# PC.net
KiCad netlist of a schematic drawn in Altium Designer
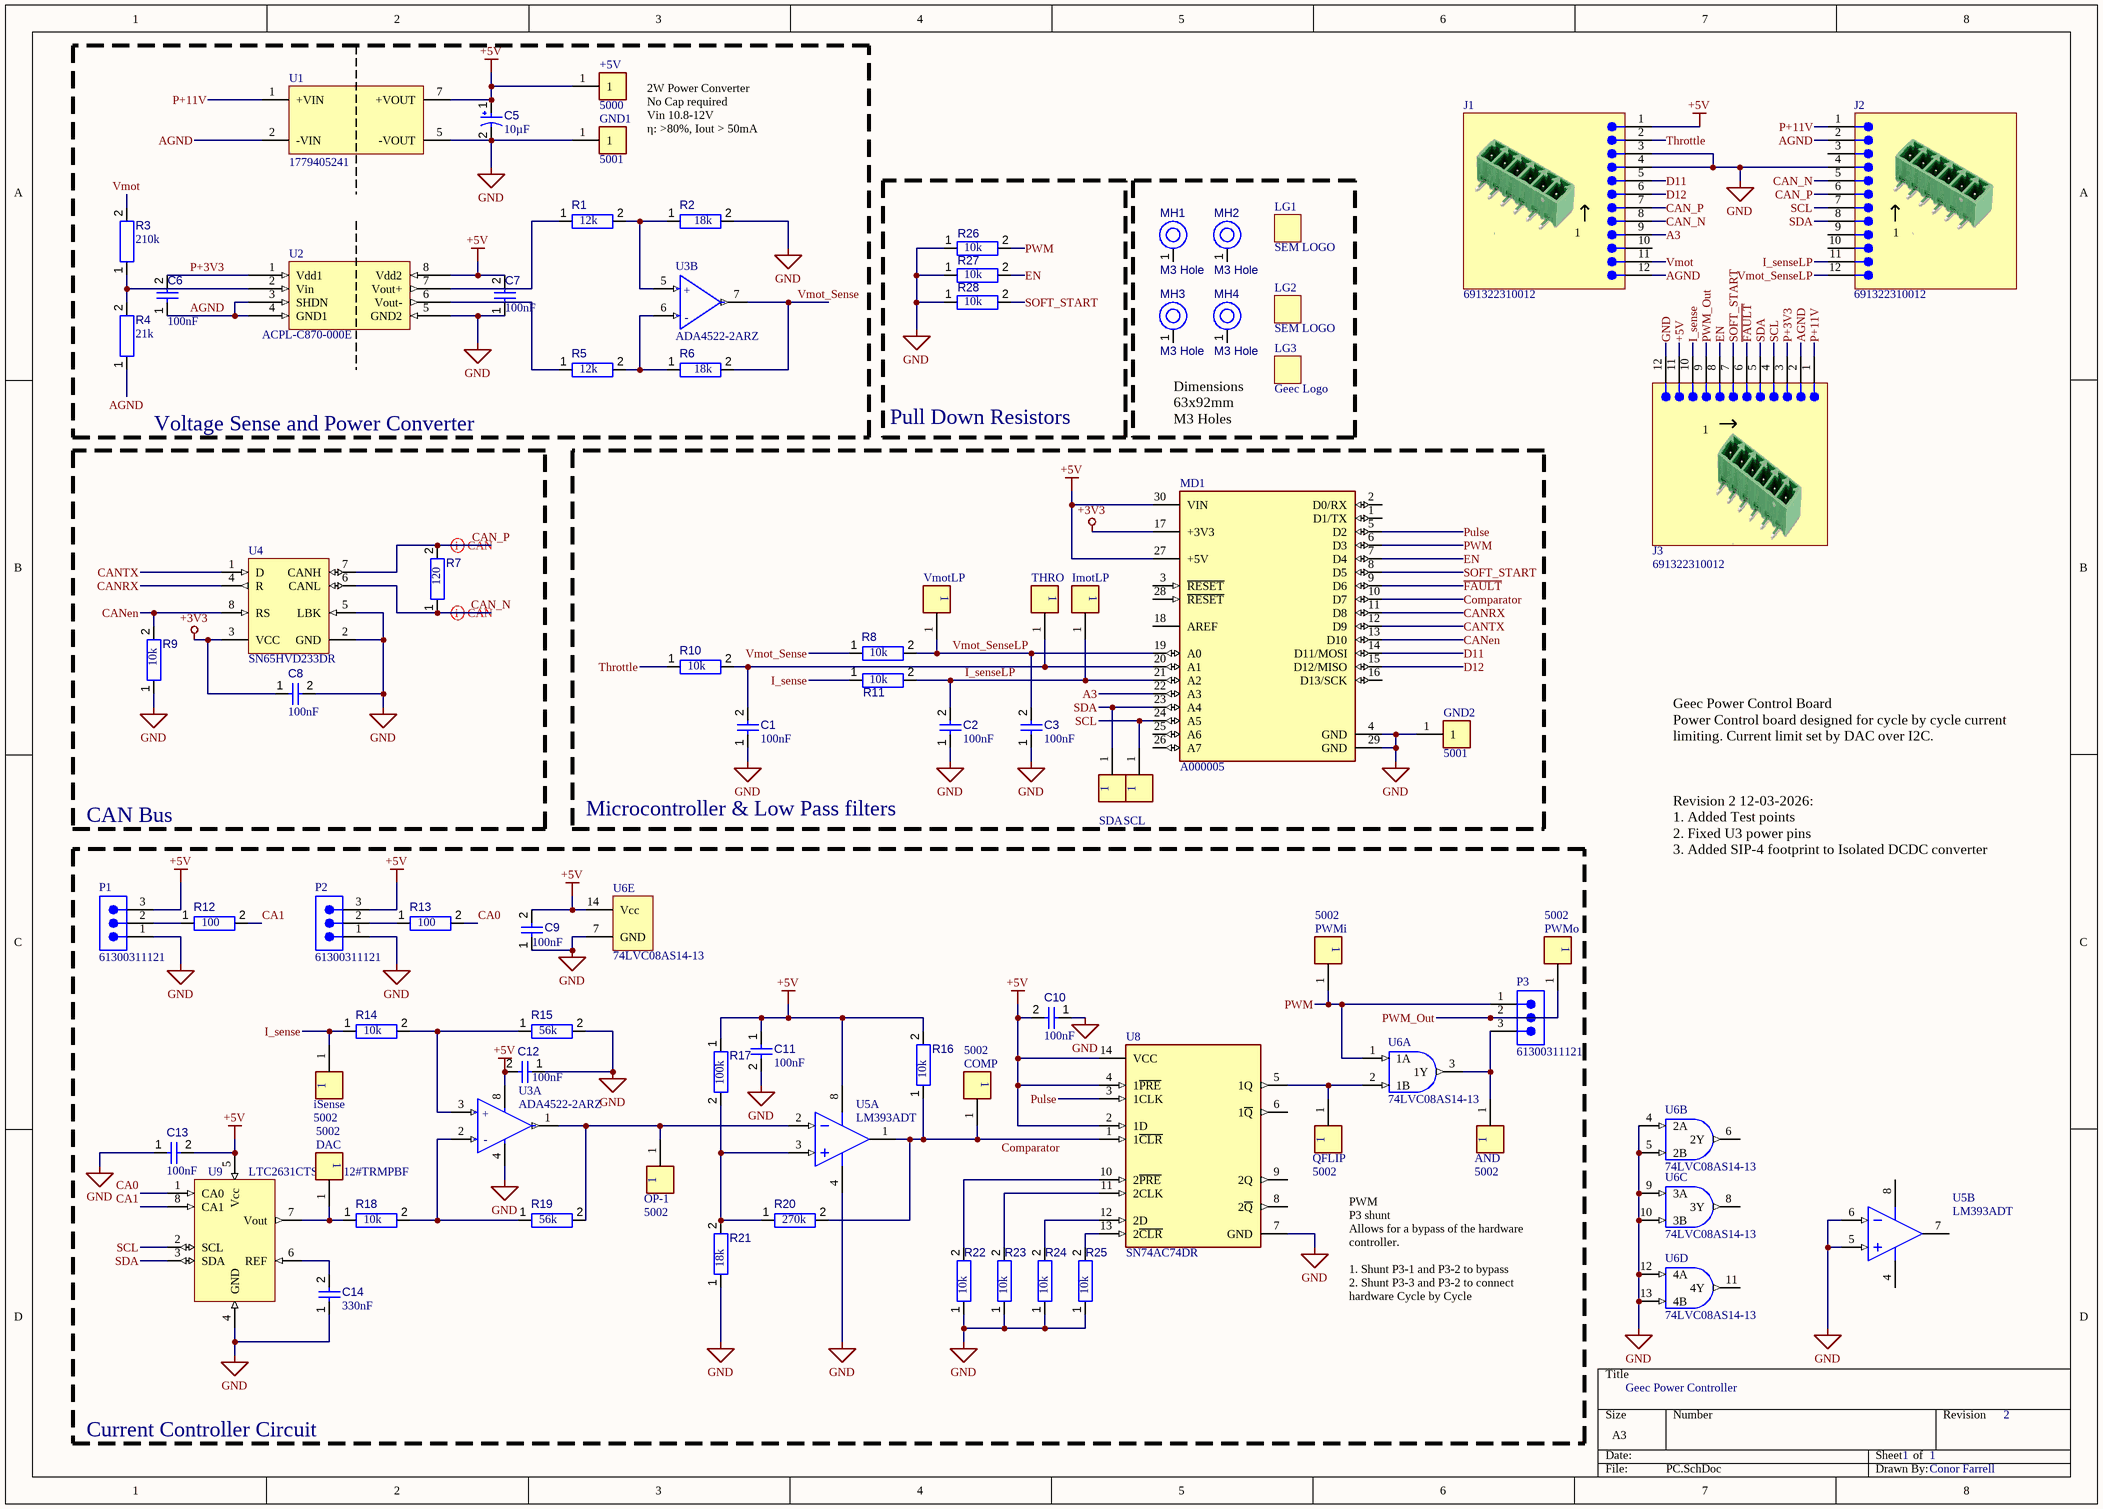
[diagram p0: PC.SchDoc]

(export (version "E")
  (design (tool "Eeschema 10.0.6"))
  (components
    (comp (ref "+5V")
      (value "5000")
      (footprint "FP-5000-MFG")
      (description "Cable Wrap, 1/2 Inch, Polyethylene, Natural, 50 Ft, Spirap Series")
      (libsource (lib "") (part "1e4615820a309e3ce90f9e6d957b7fa_2"))
    )
    (comp (ref "AND")
      (value "5002")
      (footprint "FP-5002-MFG")
      (description "Test Point, Mini, Thm, Pc, .300 L, .100 Od, Heat Resistant Nylon 46, White")
      (libsource (lib "University of Galway") (part "1e4615820a309e3ce90f9e6d957b7fa"))
    )
    (comp (ref "C1")
      (value "100nF")
      (footprint "Cap-THT-Ceramic(7.2X2.5)")
      (description "100nF, Throughhole Film Capacitor, 5mm spacing")
      (fields (field (name "TOLERANCE") "10%") (field (name "Comment") "100n-THT"))
      (libsource (lib "University of Galway") (part "CAP-NP-2"))
    )
    (comp (ref "C2")
      (value "100nF")
      (footprint "Cap-THT-Ceramic(7.2X2.5)")
      (description "100nF, Throughhole Film Capacitor, 5mm spacing")
      (fields (field (name "TOLERANCE") "10%") (field (name "Comment") "100n-THT"))
      (libsource (lib "University of Galway") (part "CAP-NP-2"))
    )
    (comp (ref "C3")
      (value "100nF")
      (footprint "Cap-THT-Ceramic(7.2X2.5)")
      (description "100nF, Throughhole Film Capacitor, 5mm spacing")
      (fields (field (name "TOLERANCE") "10%") (field (name "Comment") "100n-THT"))
      (libsource (lib "University of Galway") (part "CAP-NP-2"))
    )
    (comp (ref "C5")
      (value "10µF")
      (footprint "CAPPR55-200-1100X500X1200")
      (description "Aluminum Electrolytic Capacitor, 10 uF, +/- 20%, 50 V, -40 to 85 degC, 2-Pin THD, RoHS, Bulk")
      (fields (field (name "MANUFACTURER") "Panasonic") (field (name "TOLERANCE") "20%"))
      (libsource (lib "University of Galway") (part "CAP-P-2"))
    )
    (comp (ref "C6")
      (value "100nF")
      (footprint "Cap-THT-Ceramic(7.2X2.5)")
      (description "100nF, Throughhole Film Capacitor, 5mm spacing")
      (fields (field (name "TOLERANCE") "10%") (field (name "Comment") "100n-THT"))
      (libsource (lib "University of Galway") (part "CAP-NP-2"))
    )
    (comp (ref "C7")
      (value "100nF")
      (footprint "Cap-THT-Ceramic(7.2X2.5)")
      (description "100nF, Throughhole Film Capacitor, 5mm spacing")
      (fields (field (name "TOLERANCE") "10%") (field (name "Comment") "100n-THT"))
      (libsource (lib "University of Galway") (part "CAP-NP-2"))
    )
    (comp (ref "C8")
      (value "100nF")
      (footprint "Cap-THT-Ceramic(7.2X2.5)")
      (description "100nF, Throughhole Film Capacitor, 5mm spacing")
      (fields (field (name "TOLERANCE") "10%") (field (name "Comment") "100n-THT"))
      (libsource (lib "University of Galway") (part "CAP-NP-2"))
    )
    (comp (ref "C9")
      (value "100nF")
      (footprint "Cap-THT-Ceramic(7.2X2.5)")
      (description "100nF, Throughhole Film Capacitor, 5mm spacing")
      (fields (field (name "TOLERANCE") "10%") (field (name "Comment") "100n-THT"))
      (libsource (lib "University of Galway") (part "CAP-NP-2"))
    )
    (comp (ref "C10")
      (value "100nF")
      (footprint "Cap-THT-Ceramic(7.2X2.5)")
      (description "100nF, Throughhole Film Capacitor, 5mm spacing")
      (fields (field (name "TOLERANCE") "10%") (field (name "Comment") "100n-THT"))
      (libsource (lib "University of Galway") (part "CAP-NP-2"))
    )
    (comp (ref "C11")
      (value "100nF")
      (footprint "Cap-THT-Ceramic(7.2X2.5)")
      (description "100nF, Throughhole Film Capacitor, 5mm spacing")
      (fields (field (name "TOLERANCE") "10%") (field (name "Comment") "100n-THT"))
      (libsource (lib "University of Galway") (part "CAP-NP-2"))
    )
    (comp (ref "C12")
      (value "100nF")
      (footprint "Cap-THT-Ceramic(7.2X2.5)")
      (description "100nF, Throughhole Film Capacitor, 5mm spacing")
      (fields (field (name "TOLERANCE") "10%") (field (name "Comment") "100n-THT"))
      (libsource (lib "University of Galway") (part "CAP-NP-2"))
    )
    (comp (ref "C13")
      (value "100nF")
      (footprint "Cap-THT-Ceramic(7.2X2.5)")
      (description "100nF, Throughhole Film Capacitor, 5mm spacing")
      (fields (field (name "TOLERANCE") "10%") (field (name "Comment") "100n-THT"))
      (libsource (lib "University of Galway") (part "CAP-NP-2"))
    )
    (comp (ref "C14")
      (value "330nF")
      (footprint "Cap-THT-Ceramic(7.2X2.5)")
      (description "330nF, Throughhole Film Capacitor, 5mm spacing")
      (fields (field (name "TOLERANCE") "10%") (field (name "Comment") "330nF-THT-Film"))
      (libsource (lib "University of Galway") (part "CAP-NP-2"))
    )
    (comp (ref "COMP")
      (value "5002")
      (footprint "FP-5002-MFG")
      (description "Test Point, Mini, Thm, Pc, .300 L, .100 Od, Heat Resistant Nylon 46, White")
      (libsource (lib "") (part "1e4615820a309e3ce90f9e6d957b7fa_1"))
    )
    (comp (ref "DAC")
      (value "5002")
      (footprint "FP-5002-MFG")
      (description "Test Point, Mini, Thm, Pc, .300 L, .100 Od, Heat Resistant Nylon 46, White")
      (libsource (lib "") (part "1e4615820a309e3ce90f9e6d957b7fa_1"))
    )
    (comp (ref "GND1")
      (value "5001")
      (footprint "FP-5001-MFG")
      (description "Test Point, Mini, Thm, Pc, .300 L, .100 Od, Heat Resistant Nylon 46, Black")
      (libsource (lib "") (part "1e4615820a309e3ce90f9e6d957b7fa_2"))
    )
    (comp (ref "GND2")
      (value "5001")
      (footprint "FP-5001-MFG")
      (description "Test Point, Mini, Thm, Pc, .300 L, .100 Od, Heat Resistant Nylon 46, Black")
      (libsource (lib "") (part "1e4615820a309e3ce90f9e6d957b7fa_2"))
    )
    (comp (ref "ImotLP")
      (value "5002")
      (footprint "FP-5002-MFG")
      (description "Test Point, Mini, Thm, Pc, .300 L, .100 Od, Heat Resistant Nylon 46, White")
      (libsource (lib "") (part "1e4615820a309e3ce90f9e6d957b7fa_1"))
    )
    (comp (ref "iSense")
      (value "5002")
      (footprint "FP-5002-MFG")
      (description "Test Point, Mini, Thm, Pc, .300 L, .100 Od, Heat Resistant Nylon 46, White")
      (libsource (lib "University of Galway") (part "1e4615820a309e3ce90f9e6d957b7fa"))
    )
    (comp (ref "J1")
      (value "691322310012")
      (footprint "691322310012")
      (description "Terminal Block, R/A Header, 12Pos, Th Rohs Compliant: Yes")
      (libsource (lib "University of Galway") (part "TBL - 1R - 12P - Male"))
    )
    (comp (ref "J2")
      (value "691322310012")
      (footprint "691322310012")
      (description "Terminal Block, R/A Header, 12Pos, Th Rohs Compliant: Yes")
      (libsource (lib "") (part "TBL - 1R - 12P - Male_1"))
    )
    (comp (ref "J3")
      (value "691322310012")
      (footprint "691322310012")
      (description "Terminal Block, R/A Header, 12Pos, Th Rohs Compliant: Yes")
      (libsource (lib "University of Galway") (part "TBL - 1R - 12P - Male"))
    )
    (comp (ref "LG1")
      (value "SEM LOGO")
      (footprint "SEM LOGO-Footprint-1")
      (description "SEM Logo Required for Power Electronics")
      (libsource (lib "University of Galway") (part "SEM LOGO-Symbol-1"))
    )
    (comp (ref "LG2")
      (value "SEM LOGO")
      (footprint "SEM LOGO-Footprint-1")
      (description "SEM Logo Required for Power Electronics")
      (libsource (lib "University of Galway") (part "SEM LOGO-Symbol-1"))
    )
    (comp (ref "LG3")
      (value "Geec Logo")
      (footprint "Geec Logo-Footprint-1")
      (libsource (lib "University of Galway") (part "Geec Logo-Symbol-1"))
    )
    (comp (ref "MD1")
      (value "A000005")
      (footprint "FP-A000005-MFG")
      (description "ATmega328 Microcontroller Development Board 16MHz CPU 2KB RAM 1KB/32KB EEPROM/Flash")
      (libsource (lib "University of Galway") (part "d190c066e99afd1c6882cf92e11b2cc"))
    )
    (comp (ref "MH1")
      (value "M3 Hole")
      (footprint "M3 Hole-Footprint-1")
      (description "Hole for M3 bolt")
      (libsource (lib "University of Galway") (part "CMP-00028-00000-1"))
    )
    (comp (ref "MH2")
      (value "M3 Hole")
      (footprint "M3 Hole-Footprint-1")
      (description "Hole for M3 bolt")
      (libsource (lib "University of Galway") (part "CMP-00028-00000-1"))
    )
    (comp (ref "MH3")
      (value "M3 Hole")
      (footprint "M3 Hole-Footprint-1")
      (description "Hole for M3 bolt")
      (libsource (lib "University of Galway") (part "CMP-00028-00000-1"))
    )
    (comp (ref "MH4")
      (value "M3 Hole")
      (footprint "M3 Hole-Footprint-1")
      (description "Hole for M3 bolt")
      (libsource (lib "University of Galway") (part "CMP-00028-00000-1"))
    )
    (comp (ref "OP-1")
      (value "5002")
      (footprint "FP-5002-MFG")
      (description "Test Point, Mini, Thm, Pc, .300 L, .100 Od, Heat Resistant Nylon 46, White")
      (libsource (lib "University of Galway") (part "1e4615820a309e3ce90f9e6d957b7fa"))
    )
    (comp (ref "P1")
      (value "61300311121")
      (footprint "61300311121")
      (description "WR-PHD Pin Header, THT, Vertical, pitch 2.54mm, 1 Row, 3P")
      (fields (field (name "MANUFACTURER") "Wurth Elektronik"))
      (libsource (lib "University of Galway") (part "62000311121"))
    )
    (comp (ref "P2")
      (value "61300311121")
      (footprint "61300311121")
      (description "WR-PHD Pin Header, THT, Vertical, pitch 2.54mm, 1 Row, 3P")
      (fields (field (name "MANUFACTURER") "Wurth Elektronik"))
      (libsource (lib "University of Galway") (part "62000311121"))
    )
    (comp (ref "P3")
      (value "61300311121")
      (footprint "61300311121")
      (description "WR-PHD Pin Header, THT, Vertical, pitch 2.54mm, 1 Row, 3P")
      (fields (field (name "MANUFACTURER") "Wurth Elektronik"))
      (libsource (lib "University of Galway") (part "62000311121"))
    )
    (comp (ref "PWMi")
      (value "5002")
      (footprint "FP-5002-MFG")
      (description "Test Point, Mini, Thm, Pc, .300 L, .100 Od, Heat Resistant Nylon 46, White")
      (libsource (lib "") (part "1e4615820a309e3ce90f9e6d957b7fa_1"))
    )
    (comp (ref "PWMo")
      (value "5002")
      (footprint "FP-5002-MFG")
      (description "Test Point, Mini, Thm, Pc, .300 L, .100 Od, Heat Resistant Nylon 46, White")
      (libsource (lib "") (part "1e4615820a309e3ce90f9e6d957b7fa_1"))
    )
    (comp (ref "QFLIP")
      (value "5002")
      (footprint "FP-5002-MFG")
      (description "Test Point, Mini, Thm, Pc, .300 L, .100 Od, Heat Resistant Nylon 46, White")
      (libsource (lib "University of Galway") (part "1e4615820a309e3ce90f9e6d957b7fa"))
    )
    (comp (ref "R1")
      (value "12k")
      (footprint "RESA60-630X240")
      (description "10kOhm Resistor, Through Hole, 1/4W")
      (fields (field (name "POWER") "250mW") (field (name "TOLERANCE") "5%"))
      (libsource (lib "University of Galway") (part "RES-2"))
    )
    (comp (ref "R2")
      (value "18k")
      (footprint "RESA60-630X240")
      (description "10kOhm Resistor, Through Hole, 1/4W")
      (fields (field (name "POWER") "250mW") (field (name "TOLERANCE") "5%"))
      (libsource (lib "University of Galway") (part "RES-2"))
    )
    (comp (ref "R3")
      (value "210k")
      (footprint "RESA60-630X240")
      (description "210kOhm Resistor, Throughhole, 1/4W")
      (fields (field (name "TOLERANCE") "5%") (field (name "POWER") "250mW"))
      (libsource (lib "University of Galway") (part "RES-2"))
    )
    (comp (ref "R4")
      (value "21k")
      (footprint "RESA60-630X240")
      (description "21kOhm Resistor, Throughhole, 1/4W")
      (fields (field (name "TOLERANCE") "5%") (field (name "POWER") "250mW"))
      (libsource (lib "University of Galway") (part "RES-2"))
    )
    (comp (ref "R5")
      (value "12k")
      (footprint "RESA60-630X240")
      (description "10kOhm Resistor, Through Hole, 1/4W")
      (fields (field (name "POWER") "250mW") (field (name "TOLERANCE") "5%"))
      (libsource (lib "University of Galway") (part "RES-2"))
    )
    (comp (ref "R6")
      (value "18k")
      (footprint "RESA60-630X240")
      (description "10kOhm Resistor, Through Hole, 1/4W")
      (fields (field (name "POWER") "250mW") (field (name "TOLERANCE") "5%"))
      (libsource (lib "University of Galway") (part "RES-2"))
    )
    (comp (ref "R7")
      (value "120")
      (footprint "RESA60-630X240")
      (description "120Ohm Resistor, Through Hole, 1/4W")
      (fields (field (name "TOLERANCE") "5%") (field (name "POWER") "250mW"))
      (libsource (lib "University of Galway") (part "RES-2"))
    )
    (comp (ref "R8")
      (value "10k")
      (footprint "RESA60-630X240")
      (description "10kOhm Resistor, Through Hole, 1/4W")
      (fields (field (name "POWER") "250mW") (field (name "TOLERANCE") "5%"))
      (libsource (lib "University of Galway") (part "RES-2"))
    )
    (comp (ref "R9")
      (value "10k")
      (footprint "RESA60-630X240")
      (description "10kOhm Resistor, Through Hole, 1/4W")
      (fields (field (name "POWER") "250mW") (field (name "TOLERANCE") "5%"))
      (libsource (lib "University of Galway") (part "RES-2"))
    )
    (comp (ref "R10")
      (value "10k")
      (footprint "RESA60-630X240")
      (description "10kOhm Resistor, Through Hole, 1/4W")
      (fields (field (name "POWER") "250mW") (field (name "TOLERANCE") "5%"))
      (libsource (lib "University of Galway") (part "RES-2"))
    )
    (comp (ref "R11")
      (value "10k")
      (footprint "RESA60-630X240")
      (description "10kOhm Resistor, Through Hole, 1/4W")
      (fields (field (name "POWER") "250mW") (field (name "TOLERANCE") "5%"))
      (libsource (lib "University of Galway") (part "RES-2"))
    )
    (comp (ref "R12")
      (value "100")
      (footprint "RESA60-630X240")
      (description "100Ohm Resistor Through Hole 1/4W")
      (fields (field (name "TOLERANCE") "5%") (field (name "POWER") "250mW"))
      (libsource (lib "University of Galway") (part "RES-2"))
    )
    (comp (ref "R13")
      (value "100")
      (footprint "RESA60-630X240")
      (description "100Ohm Resistor Through Hole 1/4W")
      (fields (field (name "TOLERANCE") "5%") (field (name "POWER") "250mW"))
      (libsource (lib "University of Galway") (part "RES-2"))
    )
    (comp (ref "R14")
      (value "10k")
      (footprint "RESA60-630X240")
      (description "10kOhm Resistor, Through Hole, 1/4W")
      (fields (field (name "POWER") "250mW") (field (name "TOLERANCE") "5%"))
      (libsource (lib "University of Galway") (part "RES-2"))
    )
    (comp (ref "R15")
      (value "56k")
      (footprint "RESA60-630X240")
      (description "100kOhm Resistor, Through hole, 250mW")
      (fields (field (name "TOLERANCE") "5%") (field (name "POWER") "250mW"))
      (libsource (lib "University of Galway") (part "RES-2"))
    )
    (comp (ref "R16")
      (value "10k")
      (footprint "RESA60-630X240")
      (description "10kOhm Resistor, Through Hole, 1/4W")
      (fields (field (name "POWER") "250mW") (field (name "TOLERANCE") "5%"))
      (libsource (lib "University of Galway") (part "RES-2"))
    )
    (comp (ref "R17")
      (value "100k")
      (footprint "RESA60-630X240")
      (description "100kOhm Resistor, Through hole, 250mW")
      (fields (field (name "TOLERANCE") "5%") (field (name "POWER") "250mW"))
      (libsource (lib "University of Galway") (part "RES-2"))
    )
    (comp (ref "R18")
      (value "10k")
      (footprint "RESA60-630X240")
      (description "10kOhm Resistor, Through Hole, 1/4W")
      (fields (field (name "POWER") "250mW") (field (name "TOLERANCE") "5%"))
      (libsource (lib "University of Galway") (part "RES-2"))
    )
    (comp (ref "R19")
      (value "56k")
      (footprint "RESA60-630X240")
      (description "100kOhm Resistor, Through hole, 250mW")
      (fields (field (name "TOLERANCE") "5%") (field (name "POWER") "250mW"))
      (libsource (lib "University of Galway") (part "RES-2"))
    )
    (comp (ref "R20")
      (value "270k")
      (footprint "RESA60-630X240")
      (description "270kOhm Resistor, Through Hole, 1/4W")
      (fields (field (name "TOLERANCE") "5%") (field (name "POWER") "250mW"))
      (libsource (lib "University of Galway") (part "RES-2"))
    )
    (comp (ref "R21")
      (value "18k")
      (footprint "RESA60-630X240")
      (description "18kOhm Resistor, Through Hole, 1/4W")
      (fields (field (name "POWER") "250mW") (field (name "TOLERANCE") "5%"))
      (libsource (lib "University of Galway") (part "RES-2"))
    )
    (comp (ref "R22")
      (value "10k")
      (footprint "RESA60-630X240")
      (description "10kOhm Resistor, Through Hole, 1/4W")
      (fields (field (name "POWER") "250mW") (field (name "TOLERANCE") "5%"))
      (libsource (lib "University of Galway") (part "RES-2"))
    )
    (comp (ref "R23")
      (value "10k")
      (footprint "RESA60-630X240")
      (description "10kOhm Resistor, Through Hole, 1/4W")
      (fields (field (name "POWER") "250mW") (field (name "TOLERANCE") "5%"))
      (libsource (lib "University of Galway") (part "RES-2"))
    )
    (comp (ref "R24")
      (value "10k")
      (footprint "RESA60-630X240")
      (description "10kOhm Resistor, Through Hole, 1/4W")
      (fields (field (name "POWER") "250mW") (field (name "TOLERANCE") "5%"))
      (libsource (lib "University of Galway") (part "RES-2"))
    )
    (comp (ref "R25")
      (value "10k")
      (footprint "RESA60-630X240")
      (description "10kOhm Resistor, Through Hole, 1/4W")
      (fields (field (name "POWER") "250mW") (field (name "TOLERANCE") "5%"))
      (libsource (lib "University of Galway") (part "RES-2"))
    )
    (comp (ref "R26")
      (value "10k")
      (footprint "RESA60-630X240")
      (description "10kOhm Resistor, Through Hole, 1/4W")
      (fields (field (name "POWER") "250mW") (field (name "TOLERANCE") "5%"))
      (libsource (lib "University of Galway") (part "RES-2"))
    )
    (comp (ref "R27")
      (value "10k")
      (footprint "RESA60-630X240")
      (description "10kOhm Resistor, Through Hole, 1/4W")
      (fields (field (name "POWER") "250mW") (field (name "TOLERANCE") "5%"))
      (libsource (lib "University of Galway") (part "RES-2"))
    )
    (comp (ref "R28")
      (value "10k")
      (footprint "RESA60-630X240")
      (description "10kOhm Resistor, Through Hole, 1/4W")
      (fields (field (name "POWER") "250mW") (field (name "TOLERANCE") "5%"))
      (libsource (lib "University of Galway") (part "RES-2"))
    )
    (comp (ref "SCL")
      (value "5002")
      (footprint "FP-5002-MFG")
      (description "Test Point, Mini, Thm, Pc, .300 L, .100 Od, Heat Resistant Nylon 46, White")
      (libsource (lib "University of Galway") (part "1e4615820a309e3ce90f9e6d957b7fa"))
    )
    (comp (ref "SDA")
      (value "5002")
      (footprint "FP-5002-MFG")
      (description "Test Point, Mini, Thm, Pc, .300 L, .100 Od, Heat Resistant Nylon 46, White")
      (libsource (lib "University of Galway") (part "1e4615820a309e3ce90f9e6d957b7fa"))
    )
    (comp (ref "THRO")
      (value "5002")
      (footprint "FP-5002-MFG")
      (description "Test Point, Mini, Thm, Pc, .300 L, .100 Od, Heat Resistant Nylon 46, White")
      (libsource (lib "") (part "1e4615820a309e3ce90f9e6d957b7fa_1"))
    )
    (comp (ref "U1")
      (value "1779405241")
      (footprint "SIP-7_1779405241")
      (description "WPME-FISM Fixed Isolated Module, SIP-7, 10.8 - 13.2 Vin, 5 Vout")
      (fields (field (name "MANUFACTURER") "Wurth Elektronik"))
      (libsource (lib "University of Galway") (part "1779405341"))
    )
    (comp (ref "U2")
      (value "ACPL-C870-000E")
      (footprint "SOIC127P1150X173-8M")
      (description "IC OPAMP ISOLATION 1 CIRC 8SO Isolation Amplifier 1 Circuit Differential 8-SO Stretched")
      (libsource (lib "University of Galway") (part "ACPL-C870-000E-Symbol-1"))
    )
    (comp (ref "U3")
      (value "ADA4522-2ARZ")
      (footprint "FP-R-8-IPC_C")
      (description "IC OPAMP ZERO-DRIFT 2 CIRC 8SOIC Zero-Drift Amplifier 2 Circuit Rail-to-Rail 8-SOIC")
      (libsource (lib "University of Galway") (part "9970287e766f5f2538295826f6e31b6"))
    )
    (comp (ref "U4")
      (value "SN65HVD233DR")
      (footprint "D0008A_L")
      (description "3.3 V CAN Transceiver with Standby Mode, Loopback 8-SOIC -40 to 125")
      (libsource (lib "University of Galway") (part "TI-SN65HVD233-SOIC_D-8"))
    )
    (comp (ref "U5")
      (value "LM393ADT")
      (footprint "ONSC-SOIC-8-751-07_AJ_V")
      (description "LM393 Series Dual 36 V 100 nA SMT Low Power Voltage Comparator - SOIC-8")
      (libsource (lib "University of Galway") (part "LM393ADT"))
    )
    (comp (ref "U6")
      (value "74LVC08AS14-13")
      (footprint "SOIC127P600X173-14N")
      (description "74LVC Series 5.5 V Surface Mount Quadruple 2-Input AND Gate - SOIC-14")
      (libsource (lib "University of Galway") (part "74LVC08AS14-13-Symbol-1"))
    )
    (comp (ref "U8")
      (value "SN74AC74DR")
      (footprint "FP-D0014A-MFG")
      (description "Dual Positive-Edge-Triggered D-Type Flip-Flops With Clear and Preset 14-SOIC -40 to 85")
      (libsource (lib "University of Galway") (part "46dc5e7b01fb147492ebe6268096ef7"))
    )
    (comp (ref "U9")
      (value "LTC2631CTS8-HZ12#TRMPBF")
      (footprint "TSOP65P280X100-8N")
      (description "IC DAC 12BIT V-OUT TSOT23-8 12 Bit Digital to Analog Converter 1 TSOT-23-8")
      (libsource (lib "University of Galway") (part "LTC2631CTS8-HZ12#TRMPBF-Symbol-1"))
    )
    (comp (ref "VmotLP")
      (value "5002")
      (footprint "FP-5002-MFG")
      (description "Test Point, Mini, Thm, Pc, .300 L, .100 Od, Heat Resistant Nylon 46, White")
      (libsource (lib "") (part "1e4615820a309e3ce90f9e6d957b7fa_1"))
    )
  )
  (nets
    (net (code "1") (name "+3V3") (class "Default")
      (node (ref "C8") (pin "1") (pinfunction "1_1") (pintype "passive"))
      (node (ref "MD1") (pin "17") (pinfunction "+3V3_17") (pintype "power_in"))
      (node (ref "U4") (pin "3") (pinfunction "VCC_3") (pintype "power_in"))
    )
    (net (code "2") (name "+5V") (class "Default")
      (node (ref "+5V") (pin "1") (pinfunction "1_1") (pintype "passive"))
      (node (ref "C10") (pin "2") (pinfunction "2_2") (pintype "passive"))
      (node (ref "C11") (pin "1") (pinfunction "1_1") (pintype "passive"))
      (node (ref "C12") (pin "2") (pinfunction "2_2") (pintype "passive"))
      (node (ref "C13") (pin "2") (pinfunction "2_2") (pintype "passive"))
      (node (ref "C5") (pin "1") (pinfunction "1_1") (pintype "passive"))
      (node (ref "C7") (pin "2") (pinfunction "2_2") (pintype "passive"))
      (node (ref "C9") (pin "2") (pinfunction "2_2") (pintype "passive"))
      (node (ref "J1") (pin "1") (pinfunction "1_1") (pintype "passive"))
      (node (ref "J3") (pin "11") (pinfunction "11_11") (pintype "passive"))
      (node (ref "MD1") (pin "27") (pinfunction "+5V_27") (pintype "power_in"))
      (node (ref "MD1") (pin "30") (pinfunction "VIN_30") (pintype "power_in"))
      (node (ref "P1") (pin "3") (pinfunction "3_3") (pintype "passive"))
      (node (ref "P2") (pin "3") (pinfunction "3_3") (pintype "passive"))
      (node (ref "R16") (pin "2") (pinfunction "2_2") (pintype "passive"))
      (node (ref "R17") (pin "1") (pinfunction "1_1") (pintype "passive"))
      (node (ref "U1") (pin "7") (pinfunction "+VOUT_7") (pintype "passive"))
      (node (ref "U2") (pin "8") (pinfunction "Vdd2_8") (pintype "input"))
      (node (ref "U3") (pin "8") (pinfunction "V+_8") (pintype "power_in"))
      (node (ref "U5") (pin "8") (pinfunction "VCC_8") (pintype "power_in"))
      (node (ref "U6") (pin "14") (pinfunction "Vcc_14") (pintype "passive"))
      (node (ref "U8") (pin "14") (pinfunction "VCC_14") (pintype "power_in"))
      (node (ref "U8") (pin "2") (pinfunction "1D_2") (pintype "input"))
      (node (ref "U8") (pin "4") (pinfunction "1~{PRE}_4") (pintype "input"))
      (node (ref "U9") (pin "5") (pinfunction "Vcc_5") (pintype "input"))
    )
    (net (code "3") (name "/A3") (class "Default")
      (node (ref "J1") (pin "9") (pinfunction "9_9") (pintype "passive"))
      (node (ref "MD1") (pin "22") (pinfunction "A3_22") (pintype "bidirectional"))
    )
    (net (code "4") (name "/AGND") (class "Default")
      (node (ref "C6") (pin "1") (pinfunction "1_1") (pintype "passive"))
      (node (ref "J1") (pin "12") (pinfunction "12_12") (pintype "passive"))
      (node (ref "J2") (pin "2") (pinfunction "2_2") (pintype "passive"))
      (node (ref "J3") (pin "2") (pinfunction "2_2") (pintype "passive"))
      (node (ref "R4") (pin "1") (pinfunction "1_1") (pintype "passive"))
      (node (ref "U1") (pin "2") (pinfunction "-VIN_2") (pintype "passive"))
      (node (ref "U2") (pin "3") (pinfunction "SHDN_3") (pintype "input"))
      (node (ref "U2") (pin "4") (pinfunction "GND1_4") (pintype "input"))
    )
    (net (code "5") (name "/CA0") (class "Default")
      (node (ref "R13") (pin "2") (pinfunction "2_2") (pintype "passive"))
      (node (ref "U9") (pin "1") (pinfunction "CA0_1") (pintype "input"))
    )
    (net (code "6") (name "/CA1") (class "Default")
      (node (ref "R12") (pin "2") (pinfunction "2_2") (pintype "passive"))
      (node (ref "U9") (pin "8") (pinfunction "CA1_8") (pintype "input"))
    )
    (net (code "7") (name "/CANRX") (class "Default")
      (node (ref "MD1") (pin "11") (pinfunction "D8_11") (pintype "bidirectional"))
      (node (ref "U4") (pin "4") (pinfunction "R_4") (pintype "output"))
    )
    (net (code "8") (name "/CANTX") (class "Default")
      (node (ref "MD1") (pin "12") (pinfunction "D9_12") (pintype "bidirectional"))
      (node (ref "U4") (pin "1") (pinfunction "D_1") (pintype "input"))
    )
    (net (code "9") (name "/CAN_N") (class "Default")
      (node (ref "J1") (pin "8") (pinfunction "8_8") (pintype "passive"))
      (node (ref "J2") (pin "5") (pinfunction "5_5") (pintype "passive"))
      (node (ref "R7") (pin "1") (pinfunction "1_1") (pintype "passive"))
      (node (ref "U4") (pin "6") (pinfunction "CANL_6") (pintype "bidirectional"))
    )
    (net (code "10") (name "/CAN_P") (class "Default")
      (node (ref "J1") (pin "7") (pinfunction "7_7") (pintype "passive"))
      (node (ref "J2") (pin "6") (pinfunction "6_6") (pintype "passive"))
      (node (ref "R7") (pin "2") (pinfunction "2_2") (pintype "passive"))
      (node (ref "U4") (pin "7") (pinfunction "CANH_7") (pintype "bidirectional"))
    )
    (net (code "11") (name "/CANen") (class "Default")
      (node (ref "MD1") (pin "13") (pinfunction "D10_13") (pintype "bidirectional"))
      (node (ref "R9") (pin "2") (pinfunction "2_2") (pintype "passive"))
      (node (ref "U4") (pin "8") (pinfunction "RS_8") (pintype "input"))
    )
    (net (code "12") (name "/Comparator") (class "Default")
      (node (ref "COMP") (pin "1") (pinfunction "1_1") (pintype "passive"))
      (node (ref "MD1") (pin "10") (pinfunction "D7_10") (pintype "bidirectional"))
      (node (ref "R16") (pin "1") (pinfunction "1_1") (pintype "passive"))
      (node (ref "R20") (pin "2") (pinfunction "2_2") (pintype "passive"))
      (node (ref "U5") (pin "1") (pinfunction "OUT1_1") (pintype "tri_state"))
      (node (ref "U8") (pin "1") (pinfunction "1~{CLR}_1") (pintype "input"))
    )
    (net (code "13") (name "/D11") (class "Default")
      (node (ref "J1") (pin "5") (pinfunction "5_5") (pintype "passive"))
      (node (ref "MD1") (pin "14") (pinfunction "D11/MOSI_14") (pintype "bidirectional"))
    )
    (net (code "14") (name "/D12") (class "Default")
      (node (ref "J1") (pin "6") (pinfunction "6_6") (pintype "passive"))
      (node (ref "MD1") (pin "15") (pinfunction "D12/MISO_15") (pintype "bidirectional"))
    )
    (net (code "15") (name "/EN") (class "Default")
      (node (ref "J3") (pin "8") (pinfunction "8_8") (pintype "passive"))
      (node (ref "MD1") (pin "7") (pinfunction "D4_7") (pintype "bidirectional"))
      (node (ref "R27") (pin "2") (pinfunction "2_2") (pintype "passive"))
    )
    (net (code "16") (name "/I_sense") (class "Default")
      (node (ref "J3") (pin "10") (pinfunction "10_10") (pintype "passive"))
      (node (ref "R11") (pin "1") (pinfunction "1_1") (pintype "passive"))
      (node (ref "R14") (pin "1") (pinfunction "1_1") (pintype "passive"))
      (node (ref "iSense") (pin "1") (pinfunction "1_1") (pintype "passive"))
    )
    (net (code "17") (name "/I_senseLP") (class "Default")
      (node (ref "C2") (pin "2") (pinfunction "2_2") (pintype "passive"))
      (node (ref "ImotLP") (pin "1") (pinfunction "1_1") (pintype "passive"))
      (node (ref "J2") (pin "11") (pinfunction "11_11") (pintype "passive"))
      (node (ref "MD1") (pin "21") (pinfunction "A2_21") (pintype "bidirectional"))
      (node (ref "R11") (pin "2") (pinfunction "2_2") (pintype "passive"))
    )
    (net (code "18") (name "/P+3V3") (class "Default")
      (node (ref "C6") (pin "2") (pinfunction "2_2") (pintype "passive"))
      (node (ref "J3") (pin "3") (pinfunction "3_3") (pintype "passive"))
      (node (ref "U2") (pin "1") (pinfunction "Vdd1_1") (pintype "input"))
    )
    (net (code "19") (name "/P+11V") (class "Default")
      (node (ref "J2") (pin "1") (pinfunction "1_1") (pintype "passive"))
      (node (ref "J3") (pin "1") (pinfunction "1_1") (pintype "passive"))
      (node (ref "U1") (pin "1") (pinfunction "+VIN_1") (pintype "passive"))
    )
    (net (code "20") (name "/PWM") (class "Default")
      (node (ref "MD1") (pin "6") (pinfunction "D3_6") (pintype "bidirectional"))
      (node (ref "P3") (pin "1") (pinfunction "1_1") (pintype "passive"))
      (node (ref "PWMi") (pin "1") (pinfunction "1_1") (pintype "passive"))
      (node (ref "R26") (pin "2") (pinfunction "2_2") (pintype "passive"))
      (node (ref "U6") (pin "1") (pinfunction "1A_1") (pintype "input"))
    )
    (net (code "21") (name "/PWM_Out") (class "Default")
      (node (ref "J3") (pin "9") (pinfunction "9_9") (pintype "passive"))
      (node (ref "P3") (pin "2") (pinfunction "2_2") (pintype "passive"))
      (node (ref "PWMo") (pin "1") (pinfunction "1_1") (pintype "passive"))
    )
    (net (code "22") (name "/Pulse") (class "Default")
      (node (ref "MD1") (pin "5") (pinfunction "D2_5") (pintype "bidirectional"))
      (node (ref "U8") (pin "3") (pinfunction "1CLK_3") (pintype "input"))
    )
    (net (code "23") (name "/SCL") (class "Default")
      (node (ref "J2") (pin "7") (pinfunction "7_7") (pintype "passive"))
      (node (ref "J3") (pin "4") (pinfunction "4_4") (pintype "passive"))
      (node (ref "MD1") (pin "24") (pinfunction "A5_24") (pintype "bidirectional"))
      (node (ref "SCL") (pin "1") (pinfunction "1_1") (pintype "passive"))
      (node (ref "U9") (pin "2") (pinfunction "SCL_2") (pintype "bidirectional"))
    )
    (net (code "24") (name "/SDA") (class "Default")
      (node (ref "J2") (pin "8") (pinfunction "8_8") (pintype "passive"))
      (node (ref "J3") (pin "5") (pinfunction "5_5") (pintype "passive"))
      (node (ref "MD1") (pin "23") (pinfunction "A4_23") (pintype "bidirectional"))
      (node (ref "SDA") (pin "1") (pinfunction "1_1") (pintype "passive"))
      (node (ref "U9") (pin "3") (pinfunction "SDA_3") (pintype "bidirectional"))
    )
    (net (code "25") (name "/SOFT_START") (class "Default")
      (node (ref "J3") (pin "7") (pinfunction "7_7") (pintype "passive"))
      (node (ref "MD1") (pin "8") (pinfunction "D5_8") (pintype "bidirectional"))
      (node (ref "R28") (pin "2") (pinfunction "2_2") (pintype "passive"))
    )
    (net (code "26") (name "/Throttle") (class "Default")
      (node (ref "J1") (pin "2") (pinfunction "2_2") (pintype "passive"))
      (node (ref "R10") (pin "1") (pinfunction "1_1") (pintype "passive"))
    )
    (net (code "27") (name "/Vmot") (class "Default")
      (node (ref "J1") (pin "11") (pinfunction "11_11") (pintype "passive"))
      (node (ref "R3") (pin "2") (pinfunction "2_2") (pintype "passive"))
    )
    (net (code "28") (name "/Vmot_Sense") (class "Default")
      (node (ref "R6") (pin "2") (pinfunction "2_2") (pintype "passive"))
      (node (ref "R8") (pin "1") (pinfunction "1_1") (pintype "passive"))
      (node (ref "U3") (pin "7") (pinfunction "OUT_B_7") (pintype "output"))
    )
    (net (code "29") (name "/Vmot_SenseLP") (class "Default")
      (node (ref "C3") (pin "2") (pinfunction "2_2") (pintype "passive"))
      (node (ref "J2") (pin "12") (pinfunction "12_12") (pintype "passive"))
      (node (ref "MD1") (pin "19") (pinfunction "A0_19") (pintype "bidirectional"))
      (node (ref "R8") (pin "2") (pinfunction "2_2") (pintype "passive"))
      (node (ref "VmotLP") (pin "1") (pinfunction "1_1") (pintype "passive"))
    )
    (net (code "30") (name "/~{FAULT}") (class "Default")
      (node (ref "J3") (pin "6") (pinfunction "6_6") (pintype "passive"))
      (node (ref "MD1") (pin "9") (pinfunction "D6_9") (pintype "bidirectional"))
    )
    (net (code "31") (name "GND") (class "Default")
      (node (ref "C1") (pin "1") (pinfunction "1_1") (pintype "passive"))
      (node (ref "C10") (pin "1") (pinfunction "1_1") (pintype "passive"))
      (node (ref "C11") (pin "2") (pinfunction "2_2") (pintype "passive"))
      (node (ref "C12") (pin "1") (pinfunction "1_1") (pintype "passive"))
      (node (ref "C13") (pin "1") (pinfunction "1_1") (pintype "passive"))
      (node (ref "C14") (pin "1") (pinfunction "1_1") (pintype "passive"))
      (node (ref "C2") (pin "1") (pinfunction "1_1") (pintype "passive"))
      (node (ref "C3") (pin "1") (pinfunction "1_1") (pintype "passive"))
      (node (ref "C5") (pin "2") (pinfunction "2_2") (pintype "passive"))
      (node (ref "C7") (pin "1") (pinfunction "1_1") (pintype "passive"))
      (node (ref "C8") (pin "2") (pinfunction "2_2") (pintype "passive"))
      (node (ref "C9") (pin "1") (pinfunction "1_1") (pintype "passive"))
      (node (ref "GND1") (pin "1") (pinfunction "1_1") (pintype "passive"))
      (node (ref "GND2") (pin "1") (pinfunction "1_1") (pintype "passive"))
      (node (ref "J1") (pin "3") (pinfunction "3_3") (pintype "passive"))
      (node (ref "J1") (pin "4") (pinfunction "4_4") (pintype "passive"))
      (node (ref "J2") (pin "4") (pinfunction "4_4") (pintype "passive"))
      (node (ref "J3") (pin "12") (pinfunction "12_12") (pintype "passive"))
      (node (ref "MD1") (pin "29") (pinfunction "GND_29") (pintype "power_in"))
      (node (ref "MD1") (pin "4") (pinfunction "GND_4") (pintype "power_in"))
      (node (ref "P1") (pin "1") (pinfunction "1_1") (pintype "passive"))
      (node (ref "P2") (pin "1") (pinfunction "1_1") (pintype "passive"))
      (node (ref "R15") (pin "2") (pinfunction "2_2") (pintype "passive"))
      (node (ref "R2") (pin "2") (pinfunction "2_2") (pintype "passive"))
      (node (ref "R21") (pin "1") (pinfunction "1_1") (pintype "passive"))
      (node (ref "R22") (pin "1") (pinfunction "1_1") (pintype "passive"))
      (node (ref "R23") (pin "1") (pinfunction "1_1") (pintype "passive"))
      (node (ref "R24") (pin "1") (pinfunction "1_1") (pintype "passive"))
      (node (ref "R25") (pin "1") (pinfunction "1_1") (pintype "passive"))
      (node (ref "R26") (pin "1") (pinfunction "1_1") (pintype "passive"))
      (node (ref "R27") (pin "1") (pinfunction "1_1") (pintype "passive"))
      (node (ref "R28") (pin "1") (pinfunction "1_1") (pintype "passive"))
      (node (ref "R9") (pin "1") (pinfunction "1_1") (pintype "passive"))
      (node (ref "U1") (pin "5") (pinfunction "-VOUT_5") (pintype "passive"))
      (node (ref "U2") (pin "5") (pinfunction "GND2_5") (pintype "input"))
      (node (ref "U3") (pin "4") (pinfunction "V-_4") (pintype "power_in"))
      (node (ref "U4") (pin "2") (pinfunction "GND_2") (pintype "power_in"))
      (node (ref "U4") (pin "5") (pinfunction "LBK_5") (pintype "input"))
      (node (ref "U5") (pin "4") (pinfunction "GND_4") (pintype "power_in"))
      (node (ref "U5") (pin "5") (pinfunction "IN2+_5") (pintype "input"))
      (node (ref "U5") (pin "6") (pinfunction "IN2-_6") (pintype "input"))
      (node (ref "U6") (pin "10") (pinfunction "3B_10") (pintype "input"))
      (node (ref "U6") (pin "12") (pinfunction "4A_12") (pintype "input"))
      (node (ref "U6") (pin "13") (pinfunction "4B_13") (pintype "input"))
      (node (ref "U6") (pin "4") (pinfunction "2A_4") (pintype "input"))
      (node (ref "U6") (pin "5") (pinfunction "2B_5") (pintype "input"))
      (node (ref "U6") (pin "7") (pinfunction "GND_7") (pintype "passive"))
      (node (ref "U6") (pin "9") (pinfunction "3A_9") (pintype "input"))
      (node (ref "U8") (pin "7") (pinfunction "GND_7") (pintype "power_in"))
      (node (ref "U9") (pin "4") (pinfunction "GND_4") (pintype "input"))
    )
    (net (code "32") (name "Net-(MD1-A1)") (class "Default")
      (node (ref "C1") (pin "2") (pinfunction "2_2") (pintype "passive"))
      (node (ref "MD1") (pin "20") (pinfunction "A1_20") (pintype "bidirectional"))
      (node (ref "R10") (pin "2") (pinfunction "2_2") (pintype "passive"))
      (node (ref "THRO") (pin "1") (pinfunction "1_1") (pintype "passive"))
    )
    (net (code "33") (name "Net-(P1-Pad2)") (class "Default")
      (node (ref "P1") (pin "2") (pinfunction "2_2") (pintype "passive"))
      (node (ref "R12") (pin "1") (pinfunction "1_1") (pintype "passive"))
    )
    (net (code "34") (name "Net-(P2-Pad2)") (class "Default")
      (node (ref "P2") (pin "2") (pinfunction "2_2") (pintype "passive"))
      (node (ref "R13") (pin "1") (pinfunction "1_1") (pintype "passive"))
    )
    (net (code "35") (name "Net-(U2-Vin)") (class "Default")
      (node (ref "R3") (pin "1") (pinfunction "1_1") (pintype "passive"))
      (node (ref "R4") (pin "2") (pinfunction "2_2") (pintype "passive"))
      (node (ref "U2") (pin "2") (pinfunction "Vin_2") (pintype "input"))
    )
    (net (code "36") (name "Net-(U2-Vout+)") (class "Default")
      (node (ref "R1") (pin "1") (pinfunction "1_1") (pintype "passive"))
      (node (ref "U2") (pin "7") (pinfunction "Vout+_7") (pintype "output"))
    )
    (net (code "37") (name "Net-(U2-Vout-)") (class "Default")
      (node (ref "R5") (pin "1") (pinfunction "1_1") (pintype "passive"))
      (node (ref "U2") (pin "6") (pinfunction "Vout-_6") (pintype "output"))
    )
    (net (code "38") (name "Net-(U3A-+IN_A)") (class "Default")
      (node (ref "R14") (pin "2") (pinfunction "2_2") (pintype "passive"))
      (node (ref "R15") (pin "1") (pinfunction "1_1") (pintype "passive"))
      (node (ref "U3") (pin "3") (pinfunction "+IN_A_3") (pintype "input"))
    )
    (net (code "39") (name "Net-(U3A--IN_A)") (class "Default")
      (node (ref "R18") (pin "2") (pinfunction "2_2") (pintype "passive"))
      (node (ref "R19") (pin "1") (pinfunction "1_1") (pintype "passive"))
      (node (ref "U3") (pin "2") (pinfunction "-IN_A_2") (pintype "input"))
    )
    (net (code "40") (name "Net-(U3A-OUT_A)") (class "Default")
      (node (ref "OP-1") (pin "1") (pinfunction "1_1") (pintype "passive"))
      (node (ref "R19") (pin "2") (pinfunction "2_2") (pintype "passive"))
      (node (ref "U3") (pin "1") (pinfunction "OUT_A_1") (pintype "output"))
      (node (ref "U5") (pin "2") (pinfunction "IN1-_2") (pintype "input"))
    )
    (net (code "41") (name "Net-(U3B-+IN_B)") (class "Default")
      (node (ref "R1") (pin "2") (pinfunction "2_2") (pintype "passive"))
      (node (ref "R2") (pin "1") (pinfunction "1_1") (pintype "passive"))
      (node (ref "U3") (pin "5") (pinfunction "+IN_B_5") (pintype "input"))
    )
    (net (code "42") (name "Net-(U3B--IN_B)") (class "Default")
      (node (ref "R5") (pin "2") (pinfunction "2_2") (pintype "passive"))
      (node (ref "R6") (pin "1") (pinfunction "1_1") (pintype "passive"))
      (node (ref "U3") (pin "6") (pinfunction "-IN_B_6") (pintype "input"))
    )
    (net (code "43") (name "Net-(U5A-IN1+)") (class "Default")
      (node (ref "R17") (pin "2") (pinfunction "2_2") (pintype "passive"))
      (node (ref "R20") (pin "1") (pinfunction "1_1") (pintype "passive"))
      (node (ref "R21") (pin "2") (pinfunction "2_2") (pintype "passive"))
      (node (ref "U5") (pin "3") (pinfunction "IN1+_3") (pintype "input"))
    )
    (net (code "44") (name "Net-(U6A-1B)") (class "Default")
      (node (ref "QFLIP") (pin "1") (pinfunction "1_1") (pintype "passive"))
      (node (ref "U6") (pin "2") (pinfunction "1B_2") (pintype "input"))
      (node (ref "U8") (pin "5") (pinfunction "1Q_5") (pintype "output"))
    )
    (net (code "45") (name "Net-(U6A-1Y)") (class "Default")
      (node (ref "AND") (pin "1") (pinfunction "1_1") (pintype "passive"))
      (node (ref "P3") (pin "3") (pinfunction "3_3") (pintype "passive"))
      (node (ref "U6") (pin "3") (pinfunction "1Y_3") (pintype "output"))
    )
    (net (code "46") (name "Net-(U8-2CLK)") (class "Default")
      (node (ref "R23") (pin "2") (pinfunction "2_2") (pintype "passive"))
      (node (ref "U8") (pin "11") (pinfunction "2CLK_11") (pintype "input"))
    )
    (net (code "47") (name "Net-(U8-2D)") (class "Default")
      (node (ref "R24") (pin "2") (pinfunction "2_2") (pintype "passive"))
      (node (ref "U8") (pin "12") (pinfunction "2D_12") (pintype "input"))
    )
    (net (code "48") (name "Net-(U8-2~{CLR})") (class "Default")
      (node (ref "R25") (pin "2") (pinfunction "2_2") (pintype "passive"))
      (node (ref "U8") (pin "13") (pinfunction "2~{CLR}_13") (pintype "input"))
    )
    (net (code "49") (name "Net-(U8-2~{PRE})") (class "Default")
      (node (ref "R22") (pin "2") (pinfunction "2_2") (pintype "passive"))
      (node (ref "U8") (pin "10") (pinfunction "2~{PRE}_10") (pintype "input"))
    )
    (net (code "50") (name "Net-(U9-REF)") (class "Default")
      (node (ref "C14") (pin "2") (pinfunction "2_2") (pintype "passive"))
      (node (ref "U9") (pin "6") (pinfunction "REF_6") (pintype "input"))
    )
    (net (code "51") (name "Net-(U9-Vout)") (class "Default")
      (node (ref "DAC") (pin "1") (pinfunction "1_1") (pintype "passive"))
      (node (ref "R18") (pin "1") (pinfunction "1_1") (pintype "passive"))
      (node (ref "U9") (pin "7") (pinfunction "Vout_7") (pintype "output"))
    )
    (net (code "52") (name "unconnected-(J1-Pad10)") (class "Default")
      (node (ref "J1") (pin "10") (pinfunction "10_10") (pintype "passive"))
    )
    (net (code "53") (name "unconnected-(J2-Pad3)") (class "Default")
      (node (ref "J2") (pin "3") (pinfunction "3_3") (pintype "passive"))
    )
    (net (code "54") (name "unconnected-(J2-Pad9)") (class "Default")
      (node (ref "J2") (pin "9") (pinfunction "9_9") (pintype "passive"))
    )
    (net (code "55") (name "unconnected-(J2-Pad10)") (class "Default")
      (node (ref "J2") (pin "10") (pinfunction "10_10") (pintype "passive"))
    )
    (net (code "56") (name "unconnected-(MD1-A6-Pad25)") (class "Default")
      (node (ref "MD1") (pin "25") (pinfunction "A6_25") (pintype "bidirectional"))
    )
    (net (code "57") (name "unconnected-(MD1-A7-Pad26)") (class "Default")
      (node (ref "MD1") (pin "26") (pinfunction "A7_26") (pintype "bidirectional"))
    )
    (net (code "58") (name "unconnected-(MD1-AREF-Pad18)") (class "Default")
      (node (ref "MD1") (pin "18") (pinfunction "AREF_18") (pintype "passive"))
    )
    (net (code "59") (name "unconnected-(MD1-D0{slash}RX-Pad2)") (class "Default")
      (node (ref "MD1") (pin "2") (pinfunction "D0/RX_2") (pintype "bidirectional"))
    )
    (net (code "60") (name "unconnected-(MD1-D1{slash}TX-Pad1)") (class "Default")
      (node (ref "MD1") (pin "1") (pinfunction "D1/TX_1") (pintype "bidirectional"))
    )
    (net (code "61") (name "unconnected-(MD1-D13{slash}SCK-Pad16)") (class "Default")
      (node (ref "MD1") (pin "16") (pinfunction "D13/SCK_16") (pintype "bidirectional"))
    )
    (net (code "62") (name "unconnected-(MD1-~{RESET}-Pad3)") (class "Default")
      (node (ref "MD1") (pin "3") (pinfunction "~{RESET}_3") (pintype "input"))
    )
    (net (code "63") (name "unconnected-(MD1-~{RESET}-Pad28)") (class "Default")
      (node (ref "MD1") (pin "28") (pinfunction "~{RESET}_28") (pintype "input"))
    )
    (net (code "64") (name "unconnected-(MH1-H1-Pad1)") (class "Default")
      (node (ref "MH1") (pin "1") (pinfunction "H1_1") (pintype "passive"))
    )
    (net (code "65") (name "unconnected-(MH2-H1-Pad1)") (class "Default")
      (node (ref "MH2") (pin "1") (pinfunction "H1_1") (pintype "passive"))
    )
    (net (code "66") (name "unconnected-(MH3-H1-Pad1)") (class "Default")
      (node (ref "MH3") (pin "1") (pinfunction "H1_1") (pintype "passive"))
    )
    (net (code "67") (name "unconnected-(MH4-H1-Pad1)") (class "Default")
      (node (ref "MH4") (pin "1") (pinfunction "H1_1") (pintype "passive"))
    )
    (net (code "68") (name "unconnected-(U5B-GND-Pad4)") (class "Default")
      (node (ref "U5") (pin "4") (pinfunction "GND_4") (pintype "power_in"))
    )
    (net (code "69") (name "unconnected-(U5B-OUT2-Pad7)") (class "Default")
      (node (ref "U5") (pin "7") (pinfunction "OUT2_7") (pintype "tri_state"))
    )
    (net (code "70") (name "unconnected-(U5B-VCC-Pad8)") (class "Default")
      (node (ref "U5") (pin "8") (pinfunction "VCC_8") (pintype "power_in"))
    )
    (net (code "71") (name "unconnected-(U6B-2Y-Pad6)") (class "Default")
      (node (ref "U6") (pin "6") (pinfunction "2Y_6") (pintype "output"))
    )
    (net (code "72") (name "unconnected-(U6C-3Y-Pad8)") (class "Default")
      (node (ref "U6") (pin "8") (pinfunction "3Y_8") (pintype "output"))
    )
    (net (code "73") (name "unconnected-(U6D-4Y-Pad11)") (class "Default")
      (node (ref "U6") (pin "11") (pinfunction "4Y_11") (pintype "output"))
    )
    (net (code "74") (name "unconnected-(U8-1~{Q}-Pad6)") (class "Default")
      (node (ref "U8") (pin "6") (pinfunction "1~{Q}_6") (pintype "output"))
    )
    (net (code "75") (name "unconnected-(U8-2Q-Pad9)") (class "Default")
      (node (ref "U8") (pin "9") (pinfunction "2Q_9") (pintype "output"))
    )
    (net (code "76") (name "unconnected-(U8-2~{Q}-Pad8)") (class "Default")
      (node (ref "U8") (pin "8") (pinfunction "2~{Q}_8") (pintype "output"))
    )
  )
)
